# homeboard1tmp.net
KiCad netlist of a schematic drawn in EAGLE
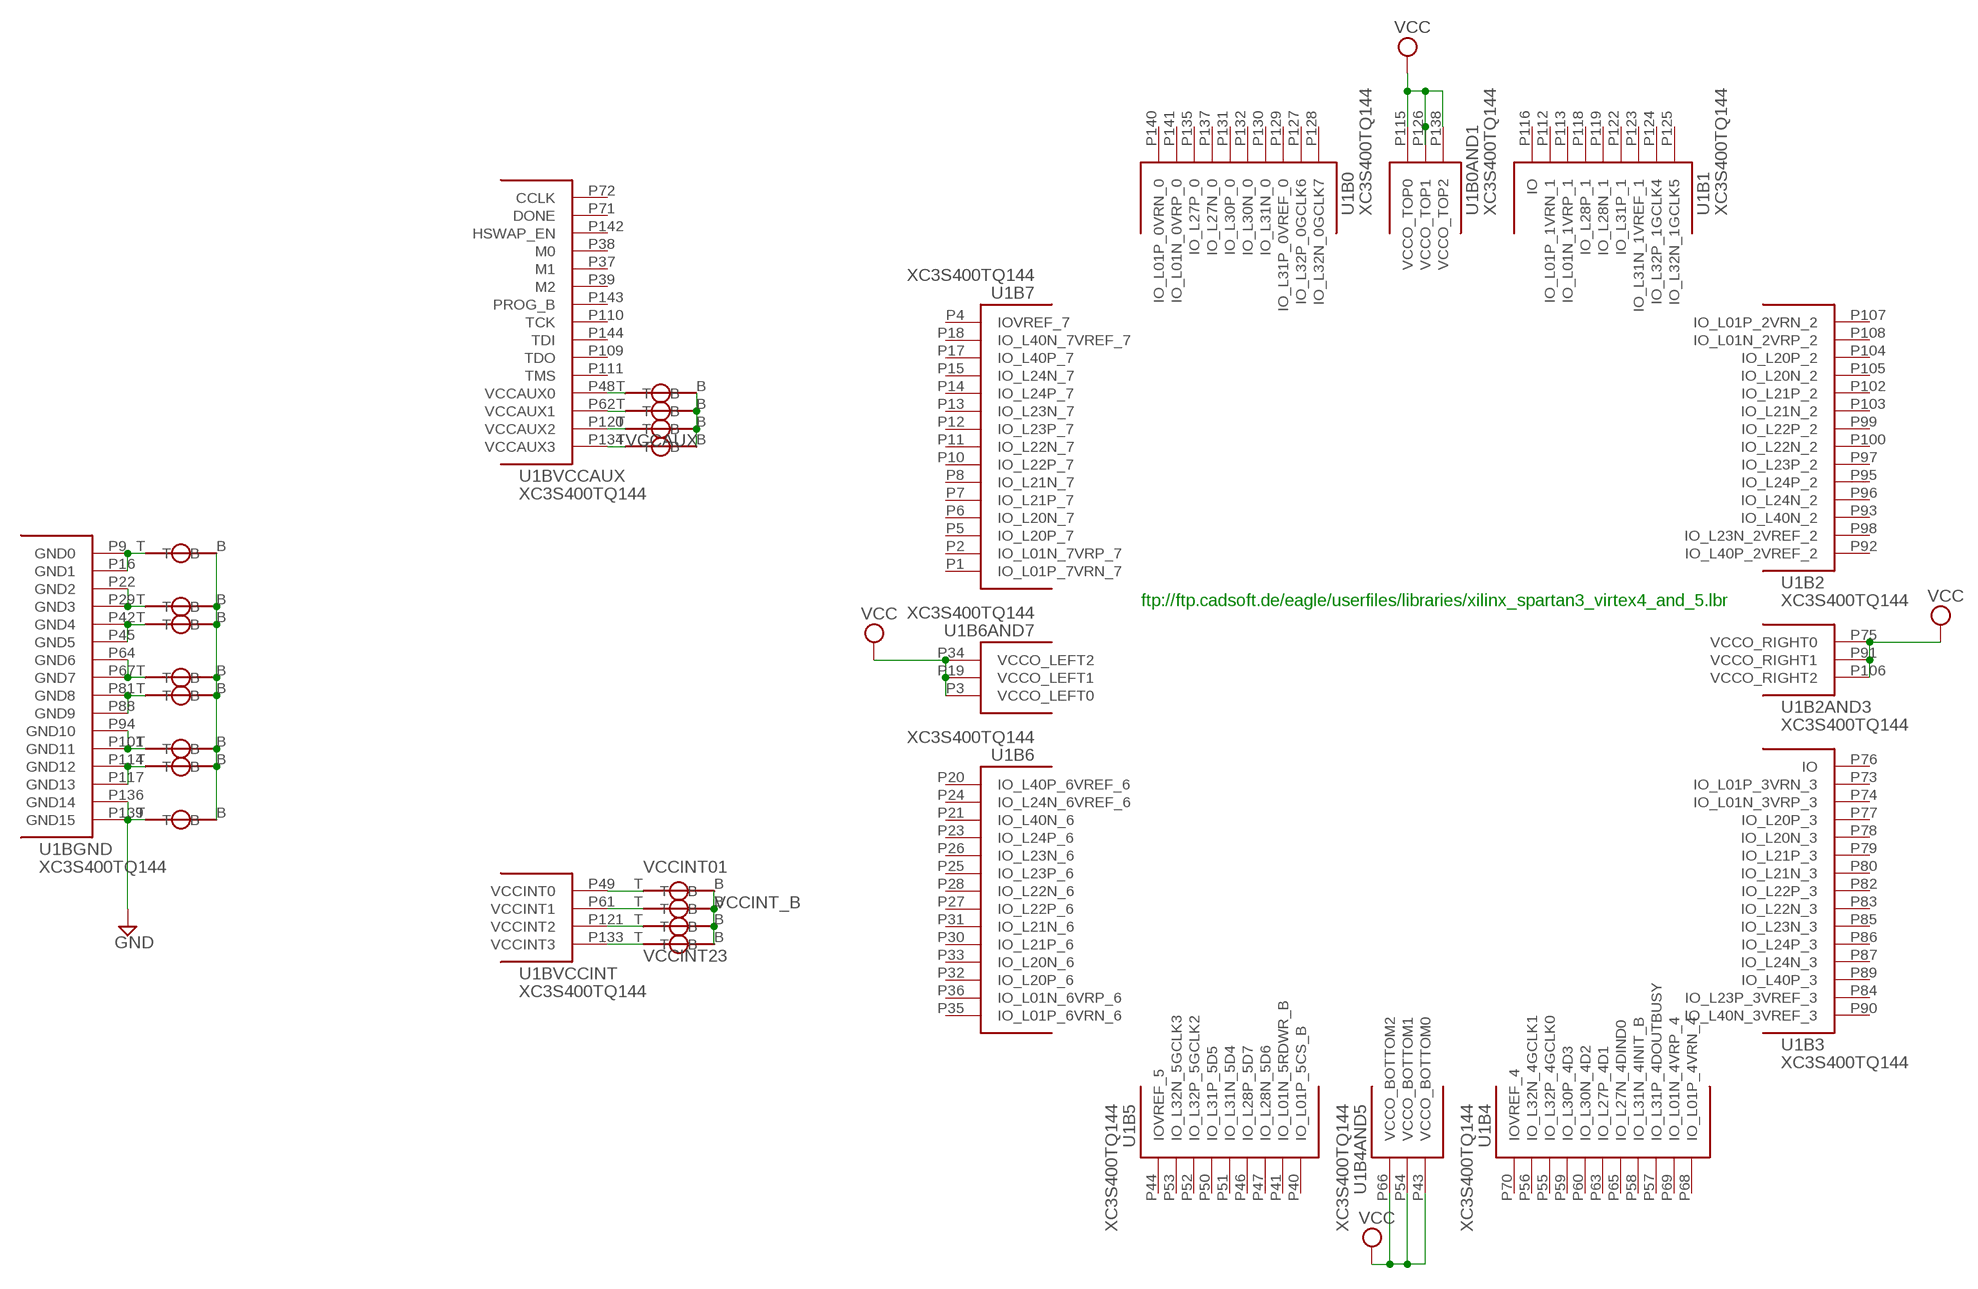
[diagram p0: schematic, sheet 1]

(export (version "E")
  (design (tool "Eeschema 10.0.6"))
  (components
    (comp (ref "U$1")
      (value "VIA_DIY")
      (footprint "eagle-import:VIA_DIY")
      (libsource (lib "eagle-import") (part "VIA_DIY"))
    )
    (comp (ref "U$2")
      (value "VIA_DIY")
      (footprint "eagle-import:VIA_DIY")
      (libsource (lib "eagle-import") (part "VIA_DIY"))
    )
    (comp (ref "U$3")
      (value "VIA_DIY")
      (footprint "eagle-import:VIA_DIY")
      (libsource (lib "eagle-import") (part "VIA_DIY"))
    )
    (comp (ref "U$4")
      (value "VIA_DIY")
      (footprint "eagle-import:VIA_DIY")
      (libsource (lib "eagle-import") (part "VIA_DIY"))
    )
    (comp (ref "U$5")
      (value "VIA_DIY")
      (footprint "eagle-import:VIA_DIY")
      (libsource (lib "eagle-import") (part "VIA_DIY"))
    )
    (comp (ref "U$8")
      (value "VIA_DIY")
      (footprint "eagle-import:VIA_DIY")
      (libsource (lib "eagle-import") (part "VIA_DIY"))
    )
    (comp (ref "U$9")
      (value "VIA_DIY")
      (footprint "eagle-import:VIA_DIY")
      (libsource (lib "eagle-import") (part "VIA_DIY"))
    )
    (comp (ref "U$12")
      (value "VIA_DIY")
      (footprint "eagle-import:VIA_DIY")
      (libsource (lib "eagle-import") (part "VIA_DIY"))
    )
    (comp (ref "U$13")
      (value "VIA_DIY")
      (footprint "eagle-import:VIA_DIY")
      (libsource (lib "eagle-import") (part "VIA_DIY"))
    )
    (comp (ref "U$16")
      (value "VIA_DIY")
      (footprint "eagle-import:VIA_DIY")
      (libsource (lib "eagle-import") (part "VIA_DIY"))
    )
    (comp (ref "U$17")
      (value "VIA_DIY")
      (footprint "eagle-import:VIA_DIY")
      (libsource (lib "eagle-import") (part "VIA_DIY"))
    )
    (comp (ref "U$20")
      (value "VIA_DIY")
      (footprint "eagle-import:VIA_DIY")
      (libsource (lib "eagle-import") (part "VIA_DIY"))
    )
    (comp (ref "U$21")
      (value "VIA_DIY")
      (footprint "eagle-import:VIA_DIY")
      (libsource (lib "eagle-import") (part "VIA_DIY"))
    )
    (comp (ref "U$22")
      (value "VIA_DIY")
      (footprint "eagle-import:VIA_DIY")
      (libsource (lib "eagle-import") (part "VIA_DIY"))
    )
    (comp (ref "U$23")
      (value "VIA_DIY")
      (footprint "eagle-import:VIA_DIY")
      (libsource (lib "eagle-import") (part "VIA_DIY"))
    )
    (comp (ref "U$24")
      (value "VIA_DIY")
      (footprint "eagle-import:VIA_DIY")
      (libsource (lib "eagle-import") (part "VIA_DIY"))
    )
    (comp (ref "U1")
      (value "XC3S400TQ144")
      (footprint "eagle-import:TQ144")
      (libsource (lib "eagle-import") (part "XC3S400TQ144"))
    )
  )
  (nets
    (net (code "1") (name "/VCCAUX") (class "Default")
      (node (ref "U$4") (pin "T") (pinfunction "T_T") (pintype "bidirectional"))
      (node (ref "U1") (pin "P120") (pinfunction "VCCAUX2_P120") (pintype "passive"))
    )
    (net (code "2") (name "/VCCINT01") (class "Default")
      (node (ref "U$1") (pin "T") (pinfunction "T_T") (pintype "bidirectional"))
      (node (ref "U1") (pin "P49") (pinfunction "VCCINT0_P49") (pintype "passive"))
    )
    (net (code "3") (name "/VCCINT23") (class "Default")
      (node (ref "U$2") (pin "T") (pinfunction "T_T") (pintype "bidirectional"))
      (node (ref "U1") (pin "P121") (pinfunction "VCCINT2_P121") (pintype "passive"))
    )
    (net (code "4") (name "/VCCINT_B") (class "Default")
      (node (ref "U$1") (pin "B") (pinfunction "B_B") (pintype "bidirectional"))
      (node (ref "U$2") (pin "B") (pinfunction "B_B") (pintype "bidirectional"))
      (node (ref "U$23") (pin "B") (pinfunction "B_B") (pintype "bidirectional"))
      (node (ref "U$24") (pin "B") (pinfunction "B_B") (pintype "bidirectional"))
    )
    (net (code "5") (name "GND") (class "Default")
      (node (ref "U$20") (pin "T") (pinfunction "T_T") (pintype "bidirectional"))
      (node (ref "U1") (pin "P136") (pinfunction "GND14_P136") (pintype "passive"))
      (node (ref "U1") (pin "P139") (pinfunction "GND15_P139") (pintype "passive"))
    )
    (net (code "6") (name "Net-(U$12-PadB)") (class "Default")
      (node (ref "U$12") (pin "B") (pinfunction "B_B") (pintype "bidirectional"))
      (node (ref "U$13") (pin "B") (pinfunction "B_B") (pintype "bidirectional"))
      (node (ref "U$16") (pin "B") (pinfunction "B_B") (pintype "bidirectional"))
      (node (ref "U$17") (pin "B") (pinfunction "B_B") (pintype "bidirectional"))
      (node (ref "U$20") (pin "B") (pinfunction "B_B") (pintype "bidirectional"))
      (node (ref "U$5") (pin "B") (pinfunction "B_B") (pintype "bidirectional"))
      (node (ref "U$8") (pin "B") (pinfunction "B_B") (pintype "bidirectional"))
      (node (ref "U$9") (pin "B") (pinfunction "B_B") (pintype "bidirectional"))
    )
    (net (code "7") (name "Net-(U$21-PadB)") (class "Default")
      (node (ref "U$21") (pin "B") (pinfunction "B_B") (pintype "bidirectional"))
      (node (ref "U$22") (pin "B") (pinfunction "B_B") (pintype "bidirectional"))
      (node (ref "U$3") (pin "B") (pinfunction "B_B") (pintype "bidirectional"))
      (node (ref "U$4") (pin "B") (pinfunction "B_B") (pintype "bidirectional"))
    )
    (net (code "8") (name "Net-(U1M-GND0)") (class "Default")
      (node (ref "U$5") (pin "T") (pinfunction "T_T") (pintype "bidirectional"))
      (node (ref "U1") (pin "P16") (pinfunction "GND1_P16") (pintype "passive"))
      (node (ref "U1") (pin "P9") (pinfunction "GND0_P9") (pintype "passive"))
    )
    (net (code "9") (name "Net-(U1M-GND2)") (class "Default")
      (node (ref "U$8") (pin "T") (pinfunction "T_T") (pintype "bidirectional"))
      (node (ref "U1") (pin "P22") (pinfunction "GND2_P22") (pintype "passive"))
      (node (ref "U1") (pin "P29") (pinfunction "GND3_P29") (pintype "passive"))
    )
    (net (code "10") (name "Net-(U1M-GND4)") (class "Default")
      (node (ref "U$9") (pin "T") (pinfunction "T_T") (pintype "bidirectional"))
      (node (ref "U1") (pin "P42") (pinfunction "GND4_P42") (pintype "passive"))
      (node (ref "U1") (pin "P45") (pinfunction "GND5_P45") (pintype "passive"))
    )
    (net (code "11") (name "Net-(U1M-GND6)") (class "Default")
      (node (ref "U$12") (pin "T") (pinfunction "T_T") (pintype "bidirectional"))
      (node (ref "U1") (pin "P64") (pinfunction "GND6_P64") (pintype "passive"))
      (node (ref "U1") (pin "P67") (pinfunction "GND7_P67") (pintype "passive"))
    )
    (net (code "12") (name "Net-(U1M-GND8)") (class "Default")
      (node (ref "U$13") (pin "T") (pinfunction "T_T") (pintype "bidirectional"))
      (node (ref "U1") (pin "P81") (pinfunction "GND8_P81") (pintype "passive"))
      (node (ref "U1") (pin "P88") (pinfunction "GND9_P88") (pintype "passive"))
    )
    (net (code "13") (name "Net-(U1M-GND10)") (class "Default")
      (node (ref "U$16") (pin "T") (pinfunction "T_T") (pintype "bidirectional"))
      (node (ref "U1") (pin "P101") (pinfunction "GND11_P101") (pintype "passive"))
      (node (ref "U1") (pin "P94") (pinfunction "GND10_P94") (pintype "passive"))
    )
    (net (code "14") (name "Net-(U1M-GND12)") (class "Default")
      (node (ref "U$17") (pin "T") (pinfunction "T_T") (pintype "bidirectional"))
      (node (ref "U1") (pin "P114") (pinfunction "GND12_P114") (pintype "passive"))
      (node (ref "U1") (pin "P117") (pinfunction "GND13_P117") (pintype "passive"))
    )
    (net (code "15") (name "Net-(U1N-VCCAUX0)") (class "Default")
      (node (ref "U$22") (pin "T") (pinfunction "T_T") (pintype "bidirectional"))
      (node (ref "U1") (pin "P48") (pinfunction "VCCAUX0_P48") (pintype "passive"))
    )
    (net (code "16") (name "Net-(U1N-VCCAUX1)") (class "Default")
      (node (ref "U$3") (pin "T") (pinfunction "T_T") (pintype "bidirectional"))
      (node (ref "U1") (pin "P62") (pinfunction "VCCAUX1_P62") (pintype "passive"))
    )
    (net (code "17") (name "Net-(U1N-VCCAUX3)") (class "Default")
      (node (ref "U$21") (pin "T") (pinfunction "T_T") (pintype "bidirectional"))
      (node (ref "U1") (pin "P134") (pinfunction "VCCAUX3_P134") (pintype "passive"))
    )
    (net (code "18") (name "Net-(U1O-VCCINT1)") (class "Default")
      (node (ref "U$23") (pin "T") (pinfunction "T_T") (pintype "bidirectional"))
      (node (ref "U1") (pin "P61") (pinfunction "VCCINT1_P61") (pintype "passive"))
    )
    (net (code "19") (name "Net-(U1O-VCCINT3)") (class "Default")
      (node (ref "U$24") (pin "T") (pinfunction "T_T") (pintype "bidirectional"))
      (node (ref "U1") (pin "P133") (pinfunction "VCCINT3_P133") (pintype "passive"))
    )
    (net (code "20") (name "VCC") (class "Default")
      (node (ref "U1") (pin "P106") (pinfunction "VCCO_RIGHT2_P106") (pintype "passive"))
      (node (ref "U1") (pin "P115") (pinfunction "VCCO_TOP0_P115") (pintype "passive"))
      (node (ref "U1") (pin "P126") (pinfunction "VCCO_TOP1_P126") (pintype "passive"))
      (node (ref "U1") (pin "P138") (pinfunction "VCCO_TOP2_P138") (pintype "passive"))
      (node (ref "U1") (pin "P19") (pinfunction "VCCO_LEFT1_P19") (pintype "passive"))
      (node (ref "U1") (pin "P3") (pinfunction "VCCO_LEFT0_P3") (pintype "passive"))
      (node (ref "U1") (pin "P34") (pinfunction "VCCO_LEFT2_P34") (pintype "passive"))
      (node (ref "U1") (pin "P43") (pinfunction "VCCO_BOTTOM0_P43") (pintype "passive"))
      (node (ref "U1") (pin "P54") (pinfunction "VCCO_BOTTOM1_P54") (pintype "passive"))
      (node (ref "U1") (pin "P66") (pinfunction "VCCO_BOTTOM2_P66") (pintype "passive"))
      (node (ref "U1") (pin "P75") (pinfunction "VCCO_RIGHT0_P75") (pintype "passive"))
      (node (ref "U1") (pin "P91") (pinfunction "VCCO_RIGHT1_P91") (pintype "passive"))
    )
    (net (code "21") (name "unconnected-(U1A-IO_L01N_0VRP_0-PadP141)") (class "Default")
      (node (ref "U1") (pin "P141") (pinfunction "IO_L01N_0VRP_0_P141") (pintype "bidirectional"))
    )
    (net (code "22") (name "unconnected-(U1A-IO_L01P_0VRN_0-PadP140)") (class "Default")
      (node (ref "U1") (pin "P140") (pinfunction "IO_L01P_0VRN_0_P140") (pintype "bidirectional"))
    )
    (net (code "23") (name "unconnected-(U1A-IO_L27N_0-PadP137)") (class "Default")
      (node (ref "U1") (pin "P137") (pinfunction "IO_L27N_0_P137") (pintype "bidirectional"))
    )
    (net (code "24") (name "unconnected-(U1A-IO_L27P_0-PadP135)") (class "Default")
      (node (ref "U1") (pin "P135") (pinfunction "IO_L27P_0_P135") (pintype "bidirectional"))
    )
    (net (code "25") (name "unconnected-(U1A-IO_L30N_0-PadP132)") (class "Default")
      (node (ref "U1") (pin "P132") (pinfunction "IO_L30N_0_P132") (pintype "bidirectional"))
    )
    (net (code "26") (name "unconnected-(U1A-IO_L30P_0-PadP131)") (class "Default")
      (node (ref "U1") (pin "P131") (pinfunction "IO_L30P_0_P131") (pintype "bidirectional"))
    )
    (net (code "27") (name "unconnected-(U1A-IO_L31N_0-PadP130)") (class "Default")
      (node (ref "U1") (pin "P130") (pinfunction "IO_L31N_0_P130") (pintype "bidirectional"))
    )
    (net (code "28") (name "unconnected-(U1A-IO_L31P_0VREF_0-PadP129)") (class "Default")
      (node (ref "U1") (pin "P129") (pinfunction "IO_L31P_0VREF_0_P129") (pintype "bidirectional"))
    )
    (net (code "29") (name "unconnected-(U1A-IO_L32N_0GCLK7-PadP128)") (class "Default")
      (node (ref "U1") (pin "P128") (pinfunction "IO_L32N_0GCLK7_P128") (pintype "bidirectional"))
    )
    (net (code "30") (name "unconnected-(U1A-IO_L32P_0GCLK6-PadP127)") (class "Default")
      (node (ref "U1") (pin "P127") (pinfunction "IO_L32P_0GCLK6_P127") (pintype "bidirectional"))
    )
    (net (code "31") (name "unconnected-(U1C-IO-PadP116)") (class "Default")
      (node (ref "U1") (pin "P116") (pinfunction "IO_P116") (pintype "bidirectional"))
    )
    (net (code "32") (name "unconnected-(U1C-IO_L01N_1VRP_1-PadP113)") (class "Default")
      (node (ref "U1") (pin "P113") (pinfunction "IO_L01N_1VRP_1_P113") (pintype "bidirectional"))
    )
    (net (code "33") (name "unconnected-(U1C-IO_L01P_1VRN_1-PadP112)") (class "Default")
      (node (ref "U1") (pin "P112") (pinfunction "IO_L01P_1VRN_1_P112") (pintype "bidirectional"))
    )
    (net (code "34") (name "unconnected-(U1C-IO_L28N_1-PadP119)") (class "Default")
      (node (ref "U1") (pin "P119") (pinfunction "IO_L28N_1_P119") (pintype "bidirectional"))
    )
    (net (code "35") (name "unconnected-(U1C-IO_L28P_1-PadP118)") (class "Default")
      (node (ref "U1") (pin "P118") (pinfunction "IO_L28P_1_P118") (pintype "bidirectional"))
    )
    (net (code "36") (name "unconnected-(U1C-IO_L31N_1VREF_1-PadP123)") (class "Default")
      (node (ref "U1") (pin "P123") (pinfunction "IO_L31N_1VREF_1_P123") (pintype "bidirectional"))
    )
    (net (code "37") (name "unconnected-(U1C-IO_L31P_1-PadP122)") (class "Default")
      (node (ref "U1") (pin "P122") (pinfunction "IO_L31P_1_P122") (pintype "bidirectional"))
    )
    (net (code "38") (name "unconnected-(U1C-IO_L32N_1GCLK5-PadP125)") (class "Default")
      (node (ref "U1") (pin "P125") (pinfunction "IO_L32N_1GCLK5_P125") (pintype "bidirectional"))
    )
    (net (code "39") (name "unconnected-(U1C-IO_L32P_1GCLK4-PadP124)") (class "Default")
      (node (ref "U1") (pin "P124") (pinfunction "IO_L32P_1GCLK4_P124") (pintype "bidirectional"))
    )
    (net (code "40") (name "unconnected-(U1D-IO_L01N_2VRP_2-PadP108)") (class "Default")
      (node (ref "U1") (pin "P108") (pinfunction "IO_L01N_2VRP_2_P108") (pintype "bidirectional"))
    )
    (net (code "41") (name "unconnected-(U1D-IO_L01P_2VRN_2-PadP107)") (class "Default")
      (node (ref "U1") (pin "P107") (pinfunction "IO_L01P_2VRN_2_P107") (pintype "bidirectional"))
    )
    (net (code "42") (name "unconnected-(U1D-IO_L20N_2-PadP105)") (class "Default")
      (node (ref "U1") (pin "P105") (pinfunction "IO_L20N_2_P105") (pintype "bidirectional"))
    )
    (net (code "43") (name "unconnected-(U1D-IO_L20P_2-PadP104)") (class "Default")
      (node (ref "U1") (pin "P104") (pinfunction "IO_L20P_2_P104") (pintype "bidirectional"))
    )
    (net (code "44") (name "unconnected-(U1D-IO_L21N_2-PadP103)") (class "Default")
      (node (ref "U1") (pin "P103") (pinfunction "IO_L21N_2_P103") (pintype "bidirectional"))
    )
    (net (code "45") (name "unconnected-(U1D-IO_L21P_2-PadP102)") (class "Default")
      (node (ref "U1") (pin "P102") (pinfunction "IO_L21P_2_P102") (pintype "bidirectional"))
    )
    (net (code "46") (name "unconnected-(U1D-IO_L22N_2-PadP100)") (class "Default")
      (node (ref "U1") (pin "P100") (pinfunction "IO_L22N_2_P100") (pintype "bidirectional"))
    )
    (net (code "47") (name "unconnected-(U1D-IO_L22P_2-PadP99)") (class "Default")
      (node (ref "U1") (pin "P99") (pinfunction "IO_L22P_2_P99") (pintype "bidirectional"))
    )
    (net (code "48") (name "unconnected-(U1D-IO_L23N_2VREF_2-PadP98)") (class "Default")
      (node (ref "U1") (pin "P98") (pinfunction "IO_L23N_2VREF_2_P98") (pintype "bidirectional"))
    )
    (net (code "49") (name "unconnected-(U1D-IO_L23P_2-PadP97)") (class "Default")
      (node (ref "U1") (pin "P97") (pinfunction "IO_L23P_2_P97") (pintype "bidirectional"))
    )
    (net (code "50") (name "unconnected-(U1D-IO_L24N_2-PadP96)") (class "Default")
      (node (ref "U1") (pin "P96") (pinfunction "IO_L24N_2_P96") (pintype "bidirectional"))
    )
    (net (code "51") (name "unconnected-(U1D-IO_L24P_2-PadP95)") (class "Default")
      (node (ref "U1") (pin "P95") (pinfunction "IO_L24P_2_P95") (pintype "bidirectional"))
    )
    (net (code "52") (name "unconnected-(U1D-IO_L40N_2-PadP93)") (class "Default")
      (node (ref "U1") (pin "P93") (pinfunction "IO_L40N_2_P93") (pintype "bidirectional"))
    )
    (net (code "53") (name "unconnected-(U1D-IO_L40P_2VREF_2-PadP92)") (class "Default")
      (node (ref "U1") (pin "P92") (pinfunction "IO_L40P_2VREF_2_P92") (pintype "bidirectional"))
    )
    (net (code "54") (name "unconnected-(U1F-IO-PadP76)") (class "Default")
      (node (ref "U1") (pin "P76") (pinfunction "IO_P76") (pintype "bidirectional"))
    )
    (net (code "55") (name "unconnected-(U1F-IO_L01N_3VRP_3-PadP74)") (class "Default")
      (node (ref "U1") (pin "P74") (pinfunction "IO_L01N_3VRP_3_P74") (pintype "bidirectional"))
    )
    (net (code "56") (name "unconnected-(U1F-IO_L01P_3VRN_3-PadP73)") (class "Default")
      (node (ref "U1") (pin "P73") (pinfunction "IO_L01P_3VRN_3_P73") (pintype "bidirectional"))
    )
    (net (code "57") (name "unconnected-(U1F-IO_L20N_3-PadP78)") (class "Default")
      (node (ref "U1") (pin "P78") (pinfunction "IO_L20N_3_P78") (pintype "bidirectional"))
    )
    (net (code "58") (name "unconnected-(U1F-IO_L20P_3-PadP77)") (class "Default")
      (node (ref "U1") (pin "P77") (pinfunction "IO_L20P_3_P77") (pintype "bidirectional"))
    )
    (net (code "59") (name "unconnected-(U1F-IO_L21N_3-PadP80)") (class "Default")
      (node (ref "U1") (pin "P80") (pinfunction "IO_L21N_3_P80") (pintype "bidirectional"))
    )
    (net (code "60") (name "unconnected-(U1F-IO_L21P_3-PadP79)") (class "Default")
      (node (ref "U1") (pin "P79") (pinfunction "IO_L21P_3_P79") (pintype "bidirectional"))
    )
    (net (code "61") (name "unconnected-(U1F-IO_L22N_3-PadP83)") (class "Default")
      (node (ref "U1") (pin "P83") (pinfunction "IO_L22N_3_P83") (pintype "bidirectional"))
    )
    (net (code "62") (name "unconnected-(U1F-IO_L22P_3-PadP82)") (class "Default")
      (node (ref "U1") (pin "P82") (pinfunction "IO_L22P_3_P82") (pintype "bidirectional"))
    )
    (net (code "63") (name "unconnected-(U1F-IO_L23N_3-PadP85)") (class "Default")
      (node (ref "U1") (pin "P85") (pinfunction "IO_L23N_3_P85") (pintype "bidirectional"))
    )
    (net (code "64") (name "unconnected-(U1F-IO_L23P_3VREF_3-PadP84)") (class "Default")
      (node (ref "U1") (pin "P84") (pinfunction "IO_L23P_3VREF_3_P84") (pintype "bidirectional"))
    )
    (net (code "65") (name "unconnected-(U1F-IO_L24N_3-PadP87)") (class "Default")
      (node (ref "U1") (pin "P87") (pinfunction "IO_L24N_3_P87") (pintype "bidirectional"))
    )
    (net (code "66") (name "unconnected-(U1F-IO_L24P_3-PadP86)") (class "Default")
      (node (ref "U1") (pin "P86") (pinfunction "IO_L24P_3_P86") (pintype "bidirectional"))
    )
    (net (code "67") (name "unconnected-(U1F-IO_L40N_3VREF_3-PadP90)") (class "Default")
      (node (ref "U1") (pin "P90") (pinfunction "IO_L40N_3VREF_3_P90") (pintype "bidirectional"))
    )
    (net (code "68") (name "unconnected-(U1F-IO_L40P_3-PadP89)") (class "Default")
      (node (ref "U1") (pin "P89") (pinfunction "IO_L40P_3_P89") (pintype "bidirectional"))
    )
    (net (code "69") (name "unconnected-(U1G-IOVREF_4-PadP70)") (class "Default")
      (node (ref "U1") (pin "P70") (pinfunction "IOVREF_4_P70") (pintype "bidirectional"))
    )
    (net (code "70") (name "unconnected-(U1G-IO_L01N_4VRP_4-PadP69)") (class "Default")
      (node (ref "U1") (pin "P69") (pinfunction "IO_L01N_4VRP_4_P69") (pintype "bidirectional"))
    )
    (net (code "71") (name "unconnected-(U1G-IO_L01P_4VRN_4-PadP68)") (class "Default")
      (node (ref "U1") (pin "P68") (pinfunction "IO_L01P_4VRN_4_P68") (pintype "bidirectional"))
    )
    (net (code "72") (name "unconnected-(U1G-IO_L27N_4DIND0-PadP65)") (class "Default")
      (node (ref "U1") (pin "P65") (pinfunction "IO_L27N_4DIND0_P65") (pintype "bidirectional"))
    )
    (net (code "73") (name "unconnected-(U1G-IO_L27P_4D1-PadP63)") (class "Default")
      (node (ref "U1") (pin "P63") (pinfunction "IO_L27P_4D1_P63") (pintype "bidirectional"))
    )
    (net (code "74") (name "unconnected-(U1G-IO_L30N_4D2-PadP60)") (class "Default")
      (node (ref "U1") (pin "P60") (pinfunction "IO_L30N_4D2_P60") (pintype "bidirectional"))
    )
    (net (code "75") (name "unconnected-(U1G-IO_L30P_4D3-PadP59)") (class "Default")
      (node (ref "U1") (pin "P59") (pinfunction "IO_L30P_4D3_P59") (pintype "bidirectional"))
    )
    (net (code "76") (name "unconnected-(U1G-IO_L31N_4INIT_B-PadP58)") (class "Default")
      (node (ref "U1") (pin "P58") (pinfunction "IO_L31N_4INIT_B_P58") (pintype "bidirectional"))
    )
    (net (code "77") (name "unconnected-(U1G-IO_L31P_4DOUTBUSY-PadP57)") (class "Default")
      (node (ref "U1") (pin "P57") (pinfunction "IO_L31P_4DOUTBUSY_P57") (pintype "bidirectional"))
    )
    (net (code "78") (name "unconnected-(U1G-IO_L32N_4GCLK1-PadP56)") (class "Default")
      (node (ref "U1") (pin "P56") (pinfunction "IO_L32N_4GCLK1_P56") (pintype "bidirectional"))
    )
    (net (code "79") (name "unconnected-(U1G-IO_L32P_4GCLK0-PadP55)") (class "Default")
      (node (ref "U1") (pin "P55") (pinfunction "IO_L32P_4GCLK0_P55") (pintype "bidirectional"))
    )
    (net (code "80") (name "unconnected-(U1I-IOVREF_5-PadP44)") (class "Default")
      (node (ref "U1") (pin "P44") (pinfunction "IOVREF_5_P44") (pintype "bidirectional"))
    )
    (net (code "81") (name "unconnected-(U1I-IO_L01N_5RDWR_B-PadP41)") (class "Default")
      (node (ref "U1") (pin "P41") (pinfunction "IO_L01N_5RDWR_B_P41") (pintype "bidirectional"))
    )
    (net (code "82") (name "unconnected-(U1I-IO_L01P_5CS_B-PadP40)") (class "Default")
      (node (ref "U1") (pin "P40") (pinfunction "IO_L01P_5CS_B_P40") (pintype "bidirectional"))
    )
    (net (code "83") (name "unconnected-(U1I-IO_L28N_5D6-PadP47)") (class "Default")
      (node (ref "U1") (pin "P47") (pinfunction "IO_L28N_5D6_P47") (pintype "bidirectional"))
    )
    (net (code "84") (name "unconnected-(U1I-IO_L28P_5D7-PadP46)") (class "Default")
      (node (ref "U1") (pin "P46") (pinfunction "IO_L28P_5D7_P46") (pintype "bidirectional"))
    )
    (net (code "85") (name "unconnected-(U1I-IO_L31N_5D4-PadP51)") (class "Default")
      (node (ref "U1") (pin "P51") (pinfunction "IO_L31N_5D4_P51") (pintype "bidirectional"))
    )
    (net (code "86") (name "unconnected-(U1I-IO_L31P_5D5-PadP50)") (class "Default")
      (node (ref "U1") (pin "P50") (pinfunction "IO_L31P_5D5_P50") (pintype "bidirectional"))
    )
    (net (code "87") (name "unconnected-(U1I-IO_L32N_5GCLK3-PadP53)") (class "Default")
      (node (ref "U1") (pin "P53") (pinfunction "IO_L32N_5GCLK3_P53") (pintype "bidirectional"))
    )
    (net (code "88") (name "unconnected-(U1I-IO_L32P_5GCLK2-PadP52)") (class "Default")
      (node (ref "U1") (pin "P52") (pinfunction "IO_L32P_5GCLK2_P52") (pintype "bidirectional"))
    )
    (net (code "89") (name "unconnected-(U1J-IO_L01N_6VRP_6-PadP36)") (class "Default")
      (node (ref "U1") (pin "P36") (pinfunction "IO_L01N_6VRP_6_P36") (pintype "bidirectional"))
    )
    (net (code "90") (name "unconnected-(U1J-IO_L01P_6VRN_6-PadP35)") (class "Default")
      (node (ref "U1") (pin "P35") (pinfunction "IO_L01P_6VRN_6_P35") (pintype "bidirectional"))
    )
    (net (code "91") (name "unconnected-(U1J-IO_L20N_6-PadP33)") (class "Default")
      (node (ref "U1") (pin "P33") (pinfunction "IO_L20N_6_P33") (pintype "bidirectional"))
    )
    (net (code "92") (name "unconnected-(U1J-IO_L20P_6-PadP32)") (class "Default")
      (node (ref "U1") (pin "P32") (pinfunction "IO_L20P_6_P32") (pintype "bidirectional"))
    )
    (net (code "93") (name "unconnected-(U1J-IO_L21N_6-PadP31)") (class "Default")
      (node (ref "U1") (pin "P31") (pinfunction "IO_L21N_6_P31") (pintype "bidirectional"))
    )
    (net (code "94") (name "unconnected-(U1J-IO_L21P_6-PadP30)") (class "Default")
      (node (ref "U1") (pin "P30") (pinfunction "IO_L21P_6_P30") (pintype "bidirectional"))
    )
    (net (code "95") (name "unconnected-(U1J-IO_L22N_6-PadP28)") (class "Default")
      (node (ref "U1") (pin "P28") (pinfunction "IO_L22N_6_P28") (pintype "bidirectional"))
    )
    (net (code "96") (name "unconnected-(U1J-IO_L22P_6-PadP27)") (class "Default")
      (node (ref "U1") (pin "P27") (pinfunction "IO_L22P_6_P27") (pintype "bidirectional"))
    )
    (net (code "97") (name "unconnected-(U1J-IO_L23N_6-PadP26)") (class "Default")
      (node (ref "U1") (pin "P26") (pinfunction "IO_L23N_6_P26") (pintype "bidirectional"))
    )
    (net (code "98") (name "unconnected-(U1J-IO_L23P_6-PadP25)") (class "Default")
      (node (ref "U1") (pin "P25") (pinfunction "IO_L23P_6_P25") (pintype "bidirectional"))
    )
    (net (code "99") (name "unconnected-(U1J-IO_L24N_6VREF_6-PadP24)") (class "Default")
      (node (ref "U1") (pin "P24") (pinfunction "IO_L24N_6VREF_6_P24") (pintype "bidirectional"))
    )
    (net (code "100") (name "unconnected-(U1J-IO_L24P_6-PadP23)") (class "Default")
      (node (ref "U1") (pin "P23") (pinfunction "IO_L24P_6_P23") (pintype "bidirectional"))
    )
    (net (code "101") (name "unconnected-(U1J-IO_L40N_6-PadP21)") (class "Default")
      (node (ref "U1") (pin "P21") (pinfunction "IO_L40N_6_P21") (pintype "bidirectional"))
    )
    (net (code "102") (name "unconnected-(U1J-IO_L40P_6VREF_6-PadP20)") (class "Default")
      (node (ref "U1") (pin "P20") (pinfunction "IO_L40P_6VREF_6_P20") (pintype "bidirectional"))
    )
    (net (code "103") (name "unconnected-(U1L-IOVREF_7-PadP4)") (class "Default")
      (node (ref "U1") (pin "P4") (pinfunction "IOVREF_7_P4") (pintype "bidirectional"))
    )
    (net (code "104") (name "unconnected-(U1L-IO_L01N_7VRP_7-PadP2)") (class "Default")
      (node (ref "U1") (pin "P2") (pinfunction "IO_L01N_7VRP_7_P2") (pintype "bidirectional"))
    )
    (net (code "105") (name "unconnected-(U1L-IO_L01P_7VRN_7-PadP1)") (class "Default")
      (node (ref "U1") (pin "P1") (pinfunction "IO_L01P_7VRN_7_P1") (pintype "bidirectional"))
    )
    (net (code "106") (name "unconnected-(U1L-IO_L20N_7-PadP6)") (class "Default")
      (node (ref "U1") (pin "P6") (pinfunction "IO_L20N_7_P6") (pintype "bidirectional"))
    )
    (net (code "107") (name "unconnected-(U1L-IO_L20P_7-PadP5)") (class "Default")
      (node (ref "U1") (pin "P5") (pinfunction "IO_L20P_7_P5") (pintype "bidirectional"))
    )
    (net (code "108") (name "unconnected-(U1L-IO_L21N_7-PadP8)") (class "Default")
      (node (ref "U1") (pin "P8") (pinfunction "IO_L21N_7_P8") (pintype "bidirectional"))
    )
    (net (code "109") (name "unconnected-(U1L-IO_L21P_7-PadP7)") (class "Default")
      (node (ref "U1") (pin "P7") (pinfunction "IO_L21P_7_P7") (pintype "bidirectional"))
    )
    (net (code "110") (name "unconnected-(U1L-IO_L22N_7-PadP11)") (class "Default")
      (node (ref "U1") (pin "P11") (pinfunction "IO_L22N_7_P11") (pintype "bidirectional"))
    )
    (net (code "111") (name "unconnected-(U1L-IO_L22P_7-PadP10)") (class "Default")
      (node (ref "U1") (pin "P10") (pinfunction "IO_L22P_7_P10") (pintype "bidirectional"))
    )
    (net (code "112") (name "unconnected-(U1L-IO_L23N_7-PadP13)") (class "Default")
      (node (ref "U1") (pin "P13") (pinfunction "IO_L23N_7_P13") (pintype "bidirectional"))
    )
    (net (code "113") (name "unconnected-(U1L-IO_L23P_7-PadP12)") (class "Default")
      (node (ref "U1") (pin "P12") (pinfunction "IO_L23P_7_P12") (pintype "bidirectional"))
    )
    (net (code "114") (name "unconnected-(U1L-IO_L24N_7-PadP15)") (class "Default")
      (node (ref "U1") (pin "P15") (pinfunction "IO_L24N_7_P15") (pintype "bidirectional"))
    )
    (net (code "115") (name "unconnected-(U1L-IO_L24P_7-PadP14)") (class "Default")
      (node (ref "U1") (pin "P14") (pinfunction "IO_L24P_7_P14") (pintype "bidirectional"))
    )
    (net (code "116") (name "unconnected-(U1L-IO_L40N_7VREF_7-PadP18)") (class "Default")
      (node (ref "U1") (pin "P18") (pinfunction "IO_L40N_7VREF_7_P18") (pintype "bidirectional"))
    )
    (net (code "117") (name "unconnected-(U1L-IO_L40P_7-PadP17)") (class "Default")
      (node (ref "U1") (pin "P17") (pinfunction "IO_L40P_7_P17") (pintype "bidirectional"))
    )
    (net (code "118") (name "unconnected-(U1N-CCLK-PadP72)") (class "Default")
      (node (ref "U1") (pin "P72") (pinfunction "CCLK_P72") (pintype "bidirectional"))
    )
    (net (code "119") (name "unconnected-(U1N-DONE-PadP71)") (class "Default")
      (node (ref "U1") (pin "P71") (pinfunction "DONE_P71") (pintype "bidirectional"))
    )
    (net (code "120") (name "unconnected-(U1N-HSWAP_EN-PadP142)") (class "Default")
      (node (ref "U1") (pin "P142") (pinfunction "HSWAP_EN_P142") (pintype "bidirectional"))
    )
    (net (code "121") (name "unconnected-(U1N-M0-PadP38)") (class "Default")
      (node (ref "U1") (pin "P38") (pinfunction "M0_P38") (pintype "bidirectional"))
    )
    (net (code "122") (name "unconnected-(U1N-M1-PadP37)") (class "Default")
      (node (ref "U1") (pin "P37") (pinfunction "M1_P37") (pintype "bidirectional"))
    )
    (net (code "123") (name "unconnected-(U1N-M2-PadP39)") (class "Default")
      (node (ref "U1") (pin "P39") (pinfunction "M2_P39") (pintype "bidirectional"))
    )
    (net (code "124") (name "unconnected-(U1N-PROG_B-PadP143)") (class "Default")
      (node (ref "U1") (pin "P143") (pinfunction "PROG_B_P143") (pintype "bidirectional"))
    )
    (net (code "125") (name "unconnected-(U1N-TCK-PadP110)") (class "Default")
      (node (ref "U1") (pin "P110") (pinfunction "TCK_P110") (pintype "bidirectional"))
    )
    (net (code "126") (name "unconnected-(U1N-TDI-PadP144)") (class "Default")
      (node (ref "U1") (pin "P144") (pinfunction "TDI_P144") (pintype "bidirectional"))
    )
    (net (code "127") (name "unconnected-(U1N-TDO-PadP109)") (class "Default")
      (node (ref "U1") (pin "P109") (pinfunction "TDO_P109") (pintype "bidirectional"))
    )
    (net (code "128") (name "unconnected-(U1N-TMS-PadP111)") (class "Default")
      (node (ref "U1") (pin "P111") (pinfunction "TMS_P111") (pintype "bidirectional"))
    )
  )
)
